# LNA.net
KiCad netlist of a schematic drawn in Altium Designer
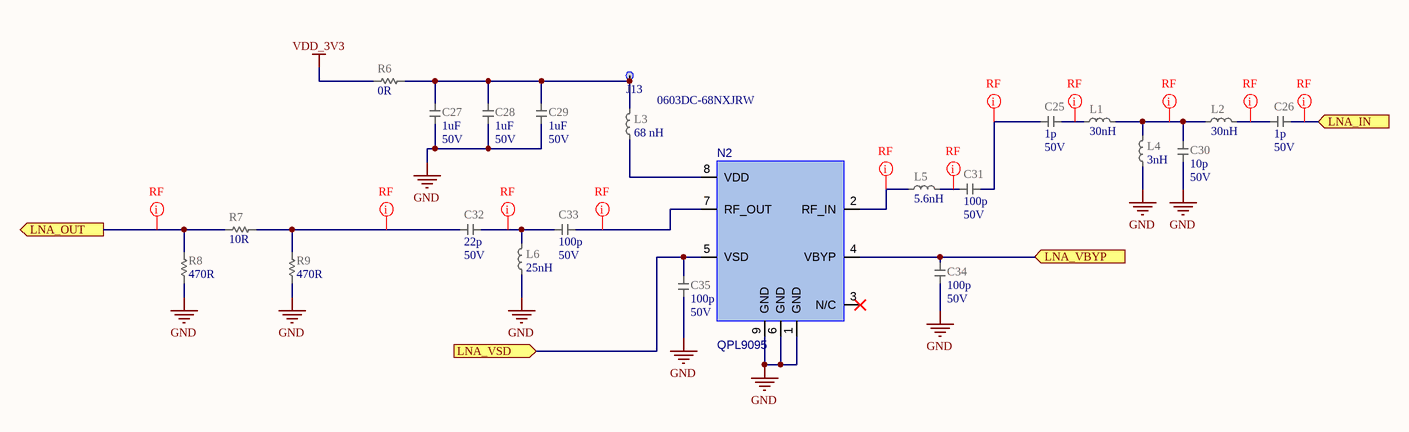
[diagram p0: LNA.SchDoc]

(export (version "E")
  (design (tool "Eeschema 10.0.6"))
  (components
    (comp (ref "C25")
      (value "1p")
      (footprint "CAP_0603_UN1Q")
      (description "CAP")
      (fields
        (field (name "MANUFACTURER") "Murata")
        (field (name "PART NUMBER") "GCM188R71H102KA37J")
        (field (name "VOLTAGE") "50V")
      )
      (libsource (lib "robo_cam") (part "CMP-001-000378-11"))
    )
    (comp (ref "C26")
      (value "1p")
      (footprint "CAP_0603_UN1Q")
      (description "CAP")
      (fields
        (field (name "MANUFACTURER") "Murata")
        (field (name "PART NUMBER") "GCM188R71H102KA37J")
        (field (name "VOLTAGE") "50V")
      )
      (libsource (lib "robo_cam") (part "CMP-001-000378-11"))
    )
    (comp (ref "C27")
      (value "1uF")
      (footprint "CAP_0603_UN1Q")
      (description "CAP")
      (fields
        (field (name "PART NUMBER") "UMK107AB7105KA-T")
        (field (name "MANUFACTURER") "Taiyo Yuden")
        (field (name "VOLTAGE") "50V")
      )
      (libsource (lib "robo_cam") (part "CMP-001-000333-14"))
    )
    (comp (ref "C28")
      (value "1uF")
      (footprint "CAP_0603_UN1Q")
      (description "CAP")
      (fields
        (field (name "PART NUMBER") "UMK107AB7105KA-T")
        (field (name "MANUFACTURER") "Taiyo Yuden")
        (field (name "VOLTAGE") "50V")
      )
      (libsource (lib "robo_cam") (part "CMP-001-000333-14"))
    )
    (comp (ref "C29")
      (value "1uF")
      (footprint "CAP_0603_UN1Q")
      (description "CAP")
      (fields
        (field (name "PART NUMBER") "UMK107AB7105KA-T")
        (field (name "MANUFACTURER") "Taiyo Yuden")
        (field (name "VOLTAGE") "50V")
      )
      (libsource (lib "robo_cam") (part "CMP-001-000333-14"))
    )
    (comp (ref "C30")
      (value "10p")
      (footprint "CAP_0603_UN1Q")
      (description "CAP")
      (fields
        (field (name "MANUFACTURER") "Murata")
        (field (name "PART NUMBER") "GCM188R71H102KA37J")
        (field (name "VOLTAGE") "50V")
      )
      (libsource (lib "robo_cam") (part "CMP-001-000378-11"))
    )
    (comp (ref "C31")
      (value "100p")
      (footprint "CAP_0603_UN1Q")
      (description "CAP")
      (fields
        (field (name "MANUFACTURER") "Murata")
        (field (name "PART NUMBER") "GCM188R71H102KA37J")
        (field (name "VOLTAGE") "50V")
      )
      (libsource (lib "robo_cam") (part "CMP-001-000378-11"))
    )
    (comp (ref "C32")
      (value "22p")
      (footprint "CAP_0603_UN1Q")
      (description "CAP")
      (fields
        (field (name "MANUFACTURER") "Murata")
        (field (name "PART NUMBER") "GCM188R71H102KA37J")
        (field (name "VOLTAGE") "50V")
      )
      (libsource (lib "robo_cam") (part "CMP-001-000378-11"))
    )
    (comp (ref "C33")
      (value "100p")
      (footprint "CAP_0603_UN1Q")
      (description "CAP")
      (fields
        (field (name "MANUFACTURER") "Murata")
        (field (name "PART NUMBER") "GCM188R71H102KA37J")
        (field (name "VOLTAGE") "50V")
      )
      (libsource (lib "robo_cam") (part "CMP-001-000378-11"))
    )
    (comp (ref "C34")
      (value "100p")
      (footprint "CAP_0603_UN1Q")
      (description "CAP")
      (fields
        (field (name "MANUFACTURER") "Murata")
        (field (name "PART NUMBER") "GCM188R71H102KA37J")
        (field (name "VOLTAGE") "50V")
      )
      (libsource (lib "robo_cam") (part "CMP-001-000378-11"))
    )
    (comp (ref "C35")
      (value "100p")
      (footprint "CAP_0603_UN1Q")
      (description "CAP")
      (fields
        (field (name "MANUFACTURER") "Murata")
        (field (name "PART NUMBER") "GCM188R71H102KA37J")
        (field (name "VOLTAGE") "50V")
      )
      (libsource (lib "robo_cam") (part "CMP-001-000378-11"))
    )
    (comp (ref "J13")
      (value "Testpoint, Surface, 1.0mm")
      (footprint "TP_1mm_UN1Q")
      (description "Testpoint 1.0mm")
      (fields (field (name "PART NUMBER") "TP 1mm"))
      (libsource (lib "robo_cam") (part "CMP-001-000153-12"))
    )
    (comp (ref "L1")
      (value "30nH")
      (footprint "IND_0603_UN1Q")
      (fields
        (field (name "MANUFACTURER") "TDK")
        (field (name "TOLERANCE") "10%")
        (field (name "MANUFACTURER PART NUMBER") "MLZ1608M100WTD25")
      )
      (libsource (lib "robo_cam") (part "CMP-034-000025-11"))
    )
    (comp (ref "L2")
      (value "30nH")
      (footprint "IND_0603_UN1Q")
      (fields
        (field (name "MANUFACTURER") "TDK")
        (field (name "TOLERANCE") "10%")
        (field (name "MANUFACTURER PART NUMBER") "MLZ1608M100WTD25")
      )
      (libsource (lib "robo_cam") (part "CMP-034-000025-11"))
    )
    (comp (ref "L3")
      (value "68 nH")
      (footprint "IND_0603_Coilcraft_0603DC")
      (description "IND High Q Ceramic Chip")
      (fields
        (field (name "PART NUMBER") "0603DC-68NXJRW")
        (field (name "TOLERANCE") "10%")
        (field (name "MANUFACTURER") "Coilcraft")
      )
      (libsource (lib "robo_cam") (part "CMP-001-001491-1"))
    )
    (comp (ref "L4")
      (value "3nH")
      (footprint "IND_0603_UN1Q")
      (fields
        (field (name "MANUFACTURER") "TDK")
        (field (name "TOLERANCE") "10%")
        (field (name "MANUFACTURER PART NUMBER") "MLZ1608M100WTD25")
      )
      (libsource (lib "robo_cam") (part "CMP-034-000025-11"))
    )
    (comp (ref "L5")
      (value "5.6nH")
      (footprint "IND_0603_UN1Q")
      (fields
        (field (name "MANUFACTURER") "TDK")
        (field (name "TOLERANCE") "10%")
        (field (name "MANUFACTURER PART NUMBER") "MLZ1608M100WTD25")
      )
      (libsource (lib "robo_cam") (part "CMP-034-000025-11"))
    )
    (comp (ref "L6")
      (value "25nH")
      (footprint "IND_0603_UN1Q")
      (fields
        (field (name "MANUFACTURER") "TDK")
        (field (name "TOLERANCE") "10%")
        (field (name "MANUFACTURER PART NUMBER") "MLZ1608M100WTD25")
      )
      (libsource (lib "robo_cam") (part "CMP-034-000025-11"))
    )
    (comp (ref "N2")
      (value "QPL9095")
      (footprint "DFN8_P50_200x200x95_QORVO")
      (description "Ultra Low-Noise, Bypass LNA")
      (fields
        (field (name "MANUFACTURER") "Qorvo")
        (field (name "PART NUMBER") "QPL9095")
        (field (name "MANUFACTURER PART NUMBER") "QPL9095SR")
      )
      (libsource (lib "robo_cam") (part "CMP-001-001198-7"))
    )
    (comp (ref "R6")
      (value "0R")
      (footprint "RES_0805_UN1Q")
      (description "RES 0805 0R.")
      (fields (field (name "MANUFACTURER") "Susumu") (field (name "TOLERANCE") "1%"))
      (libsource (lib "robo_cam") (part "CMP-001-000676-11"))
    )
    (comp (ref "R7")
      (value "10R")
      (footprint "RES_0603_UN1Q")
      (description "RES")
      (fields (field (name "MANUFACTURER") "YAGEO") (field (name "TOLERANCE") "5%"))
      (libsource (lib "robo_cam") (part "CMP-001-000441-13"))
    )
    (comp (ref "R8")
      (value "470R")
      (footprint "RES_0603_UN1Q")
      (description "RES")
      (fields (field (name "MANUFACTURER") "YAGEO") (field (name "TOLERANCE") "5%"))
      (libsource (lib "robo_cam") (part "CMP-001-000441-13"))
    )
    (comp (ref "R9")
      (value "470R")
      (footprint "RES_0603_UN1Q")
      (description "RES")
      (fields (field (name "MANUFACTURER") "YAGEO") (field (name "TOLERANCE") "5%"))
      (libsource (lib "robo_cam") (part "CMP-001-000441-13"))
    )
  )
  (nets
    (net (code "1") (name "/LNA_IN") (class "Default")
      (node (ref "C26") (pin "1") (pinfunction "1_1") (pintype "passive"))
    )
    (net (code "2") (name "/LNA_OUT") (class "Default")
      (node (ref "R7") (pin "1") (pinfunction "1_1") (pintype "passive"))
      (node (ref "R8") (pin "2") (pinfunction "2_2") (pintype "passive"))
    )
    (net (code "3") (name "/LNA_VBYP") (class "Default")
      (node (ref "C34") (pin "2") (pinfunction "2_2") (pintype "passive"))
      (node (ref "N2") (pin "4") (pinfunction "VBYP_4") (pintype "passive"))
    )
    (net (code "4") (name "/LNA_VSD") (class "Default")
      (node (ref "C35") (pin "2") (pinfunction "2_2") (pintype "passive"))
      (node (ref "N2") (pin "5") (pinfunction "VSD_5") (pintype "passive"))
    )
    (net (code "5") (name "GND") (class "Default")
      (node (ref "C27") (pin "1") (pinfunction "1_1") (pintype "passive"))
      (node (ref "C28") (pin "1") (pinfunction "1_1") (pintype "passive"))
      (node (ref "C29") (pin "1") (pinfunction "1_1") (pintype "passive"))
      (node (ref "C30") (pin "1") (pinfunction "1_1") (pintype "passive"))
      (node (ref "C34") (pin "1") (pinfunction "1_1") (pintype "passive"))
      (node (ref "C35") (pin "1") (pinfunction "1_1") (pintype "passive"))
      (node (ref "L4") (pin "1") (pinfunction "1_1") (pintype "passive"))
      (node (ref "L6") (pin "1") (pinfunction "1_1") (pintype "passive"))
      (node (ref "N2") (pin "1") (pinfunction "GND_1") (pintype "passive"))
      (node (ref "N2") (pin "6") (pinfunction "GND_6") (pintype "passive"))
      (node (ref "N2") (pin "9") (pinfunction "GND_9") (pintype "passive"))
      (node (ref "R8") (pin "1") (pinfunction "1_1") (pintype "passive"))
      (node (ref "R9") (pin "1") (pinfunction "1_1") (pintype "passive"))
    )
    (net (code "6") (name "Net-(C25-Pad1)") (class "Default")
      (node (ref "C25") (pin "1") (pinfunction "1_1") (pintype "passive"))
      (node (ref "L1") (pin "1") (pinfunction "1_1") (pintype "passive"))
    )
    (net (code "7") (name "Net-(C25-Pad2)") (class "Default")
      (node (ref "C25") (pin "2") (pinfunction "2_2") (pintype "passive"))
      (node (ref "C31") (pin "1") (pinfunction "1_1") (pintype "passive"))
    )
    (net (code "8") (name "Net-(C26-Pad2)") (class "Default")
      (node (ref "C26") (pin "2") (pinfunction "2_2") (pintype "passive"))
      (node (ref "L2") (pin "2") (pinfunction "2_2") (pintype "passive"))
    )
    (net (code "9") (name "Net-(C30-Pad2)") (class "Default")
      (node (ref "C30") (pin "2") (pinfunction "2_2") (pintype "passive"))
      (node (ref "L1") (pin "2") (pinfunction "2_2") (pintype "passive"))
      (node (ref "L2") (pin "1") (pinfunction "1_1") (pintype "passive"))
      (node (ref "L4") (pin "2") (pinfunction "2_2") (pintype "passive"))
    )
    (net (code "10") (name "Net-(C31-Pad2)") (class "Default")
      (node (ref "C31") (pin "2") (pinfunction "2_2") (pintype "passive"))
      (node (ref "L5") (pin "2") (pinfunction "2_2") (pintype "passive"))
    )
    (net (code "11") (name "Net-(C32-Pad1)") (class "Default")
      (node (ref "C32") (pin "1") (pinfunction "1_1") (pintype "passive"))
      (node (ref "C33") (pin "2") (pinfunction "2_2") (pintype "passive"))
      (node (ref "L6") (pin "2") (pinfunction "2_2") (pintype "passive"))
    )
    (net (code "12") (name "Net-(C32-Pad2)") (class "Default")
      (node (ref "C32") (pin "2") (pinfunction "2_2") (pintype "passive"))
      (node (ref "R7") (pin "2") (pinfunction "2_2") (pintype "passive"))
      (node (ref "R9") (pin "2") (pinfunction "2_2") (pintype "passive"))
    )
    (net (code "13") (name "Net-(J13-TP)") (class "Default")
      (node (ref "C27") (pin "2") (pinfunction "2_2") (pintype "passive"))
      (node (ref "C28") (pin "2") (pinfunction "2_2") (pintype "passive"))
      (node (ref "C29") (pin "2") (pinfunction "2_2") (pintype "passive"))
      (node (ref "J13") (pin "1") (pinfunction "TP_1") (pintype "passive"))
      (node (ref "L3") (pin "2") (pinfunction "2_2") (pintype "passive"))
      (node (ref "R6") (pin "2") (pinfunction "2_2") (pintype "passive"))
    )
    (net (code "14") (name "Net-(N2-RF_IN)") (class "Default")
      (node (ref "L5") (pin "1") (pinfunction "1_1") (pintype "passive"))
      (node (ref "N2") (pin "2") (pinfunction "RF_IN_2") (pintype "passive"))
    )
    (net (code "15") (name "Net-(N2-RF_OUT)") (class "Default")
      (node (ref "C33") (pin "1") (pinfunction "1_1") (pintype "passive"))
      (node (ref "N2") (pin "7") (pinfunction "RF_OUT_7") (pintype "passive"))
    )
    (net (code "16") (name "Net-(N2-VDD)") (class "Default")
      (node (ref "L3") (pin "1") (pinfunction "1_1") (pintype "passive"))
      (node (ref "N2") (pin "8") (pinfunction "VDD_8") (pintype "passive"))
    )
    (net (code "17") (name "VDD_3V3") (class "Default")
      (node (ref "R6") (pin "1") (pinfunction "1_1") (pintype "passive"))
    )
    (net (code "18") (name "unconnected-(N2-N{slash}C-Pad3)") (class "Default")
      (node (ref "N2") (pin "3") (pinfunction "N/C_3") (pintype "passive+no_connect"))
    )
  )
)
